# PCB_-_MODULE.net
KiCad netlist of a schematic drawn in EAGLE
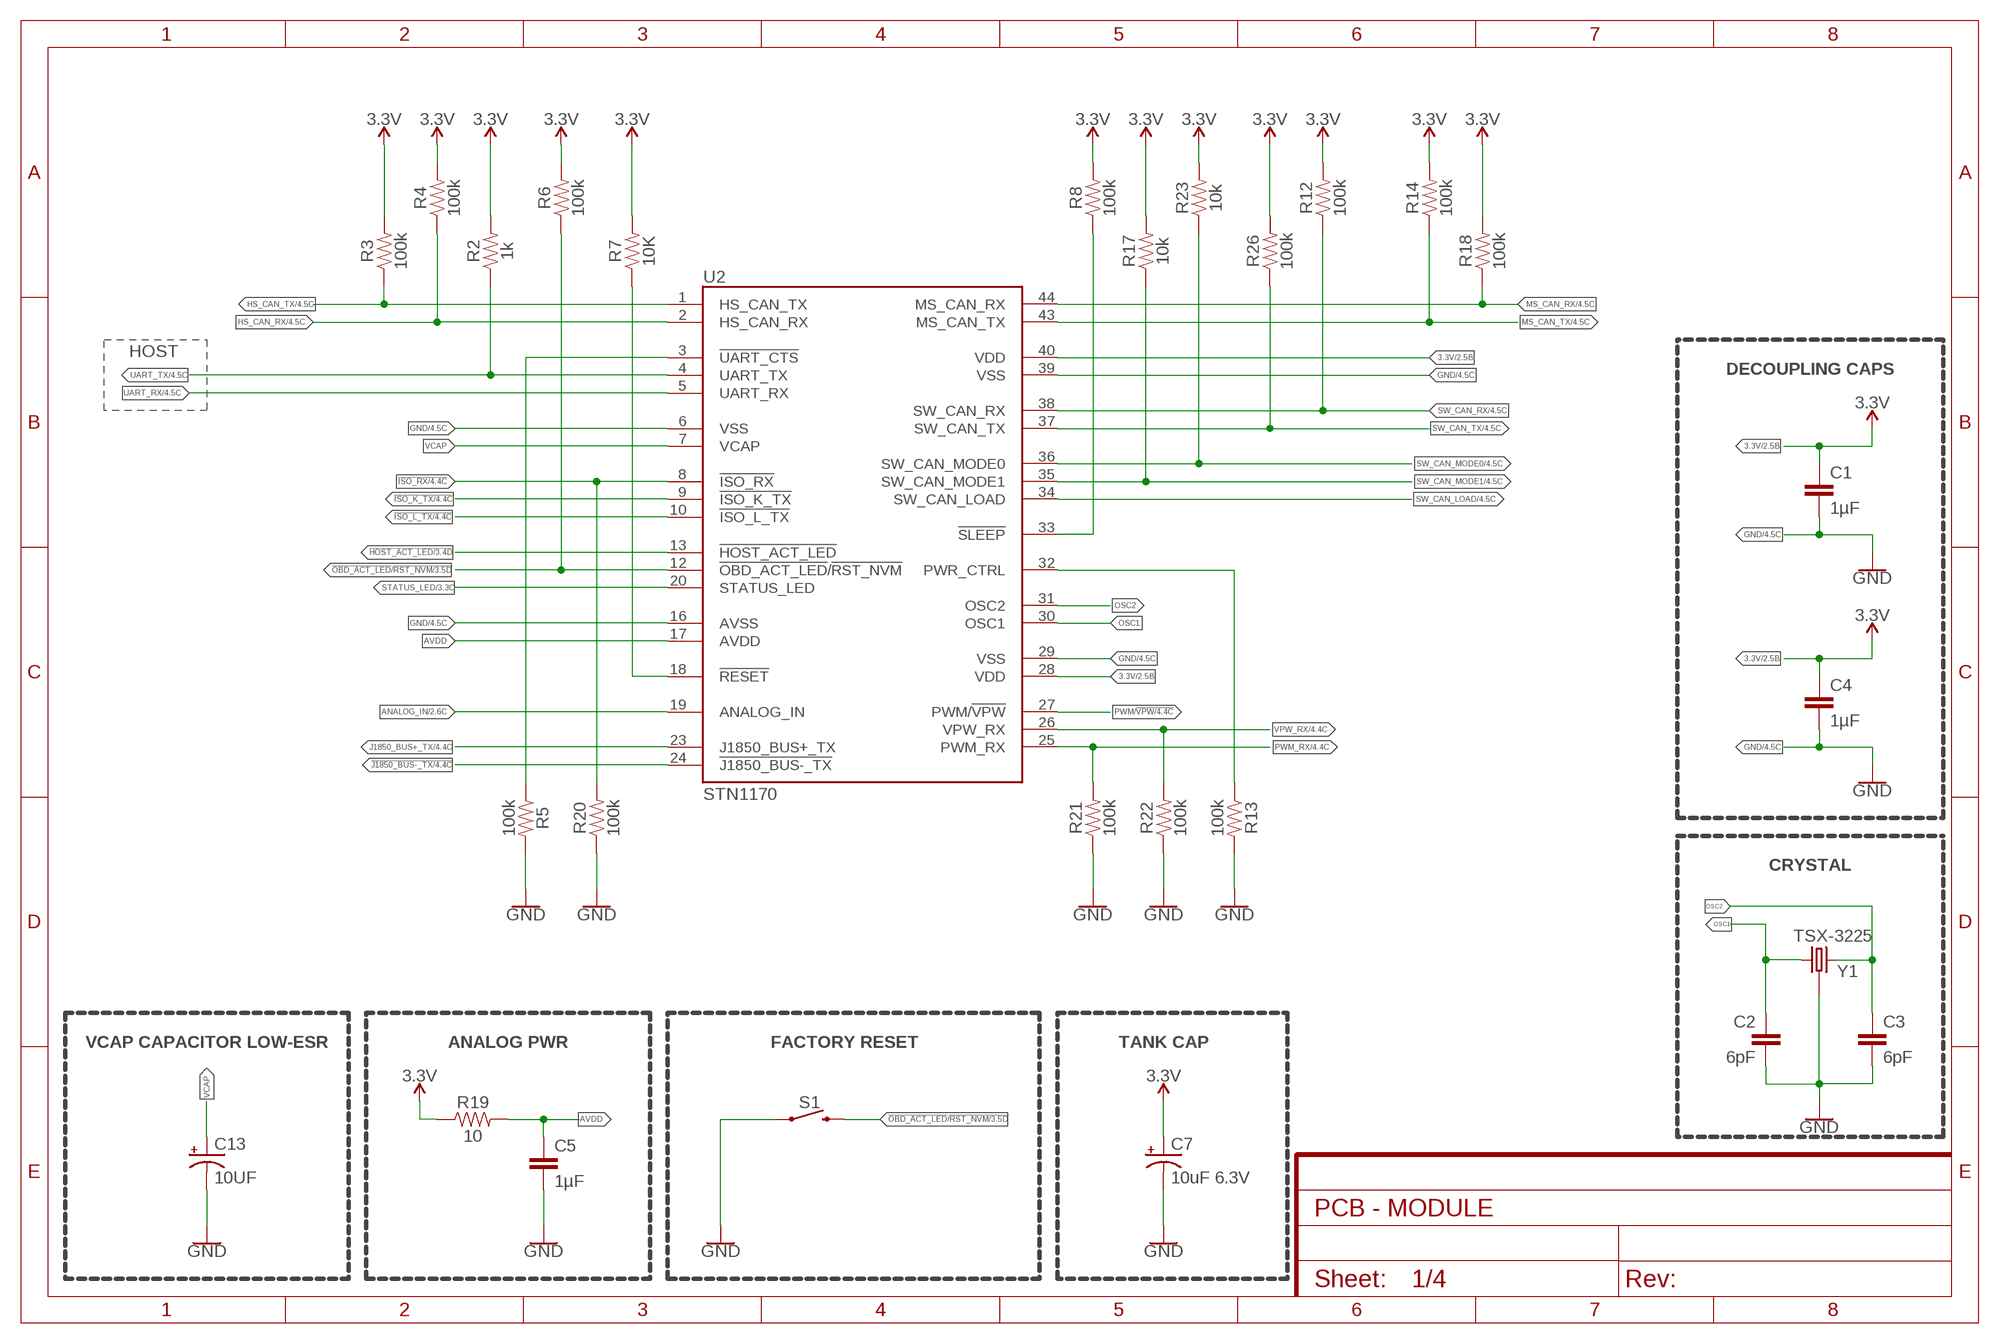
[diagram p0: schematic, sheet 1]
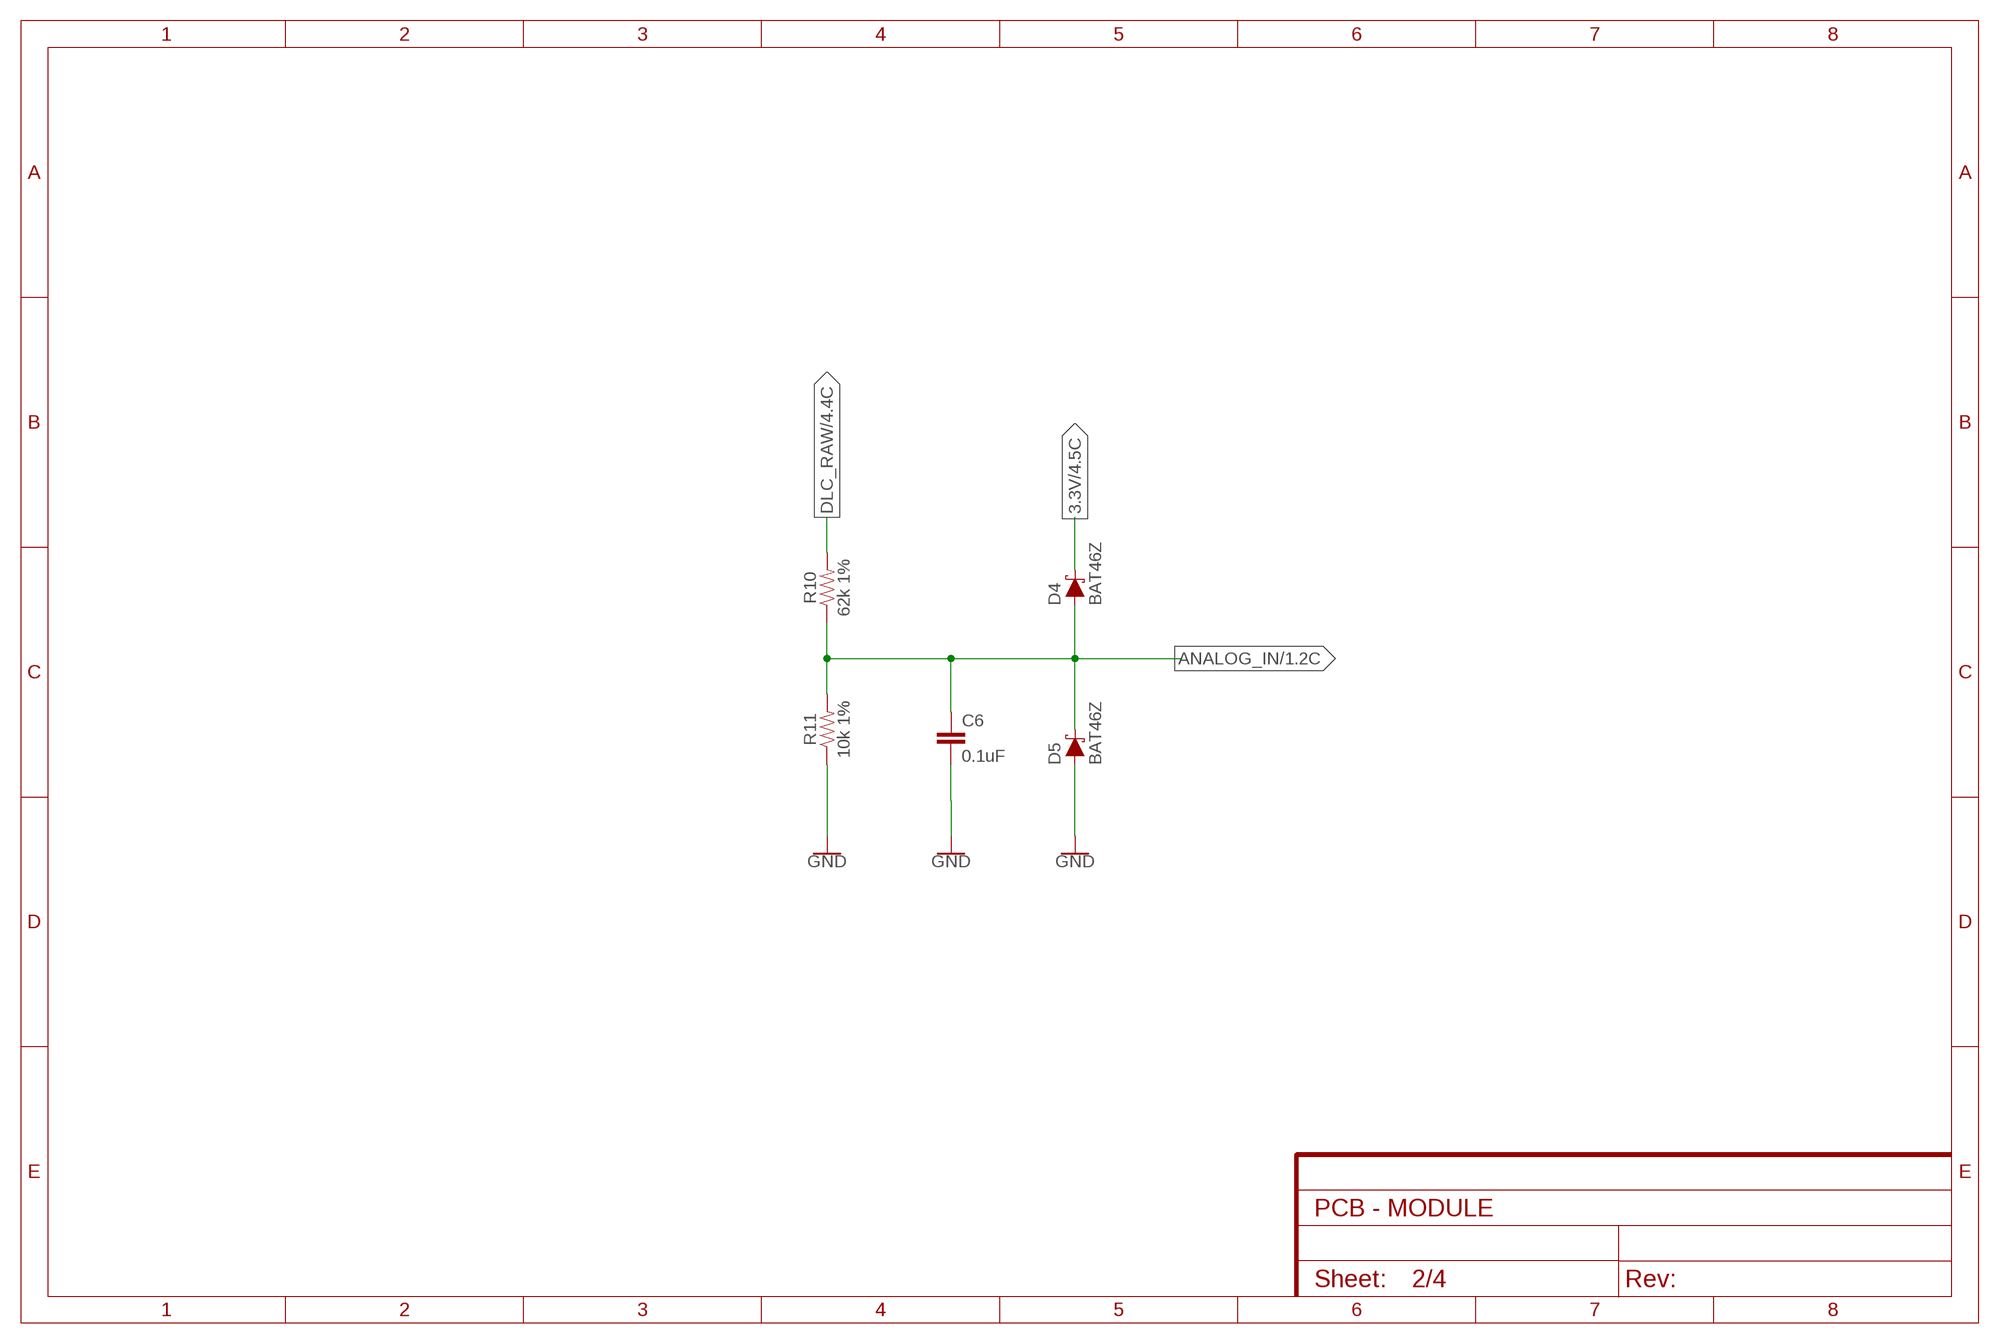
[diagram p1: schematic, sheet 2]
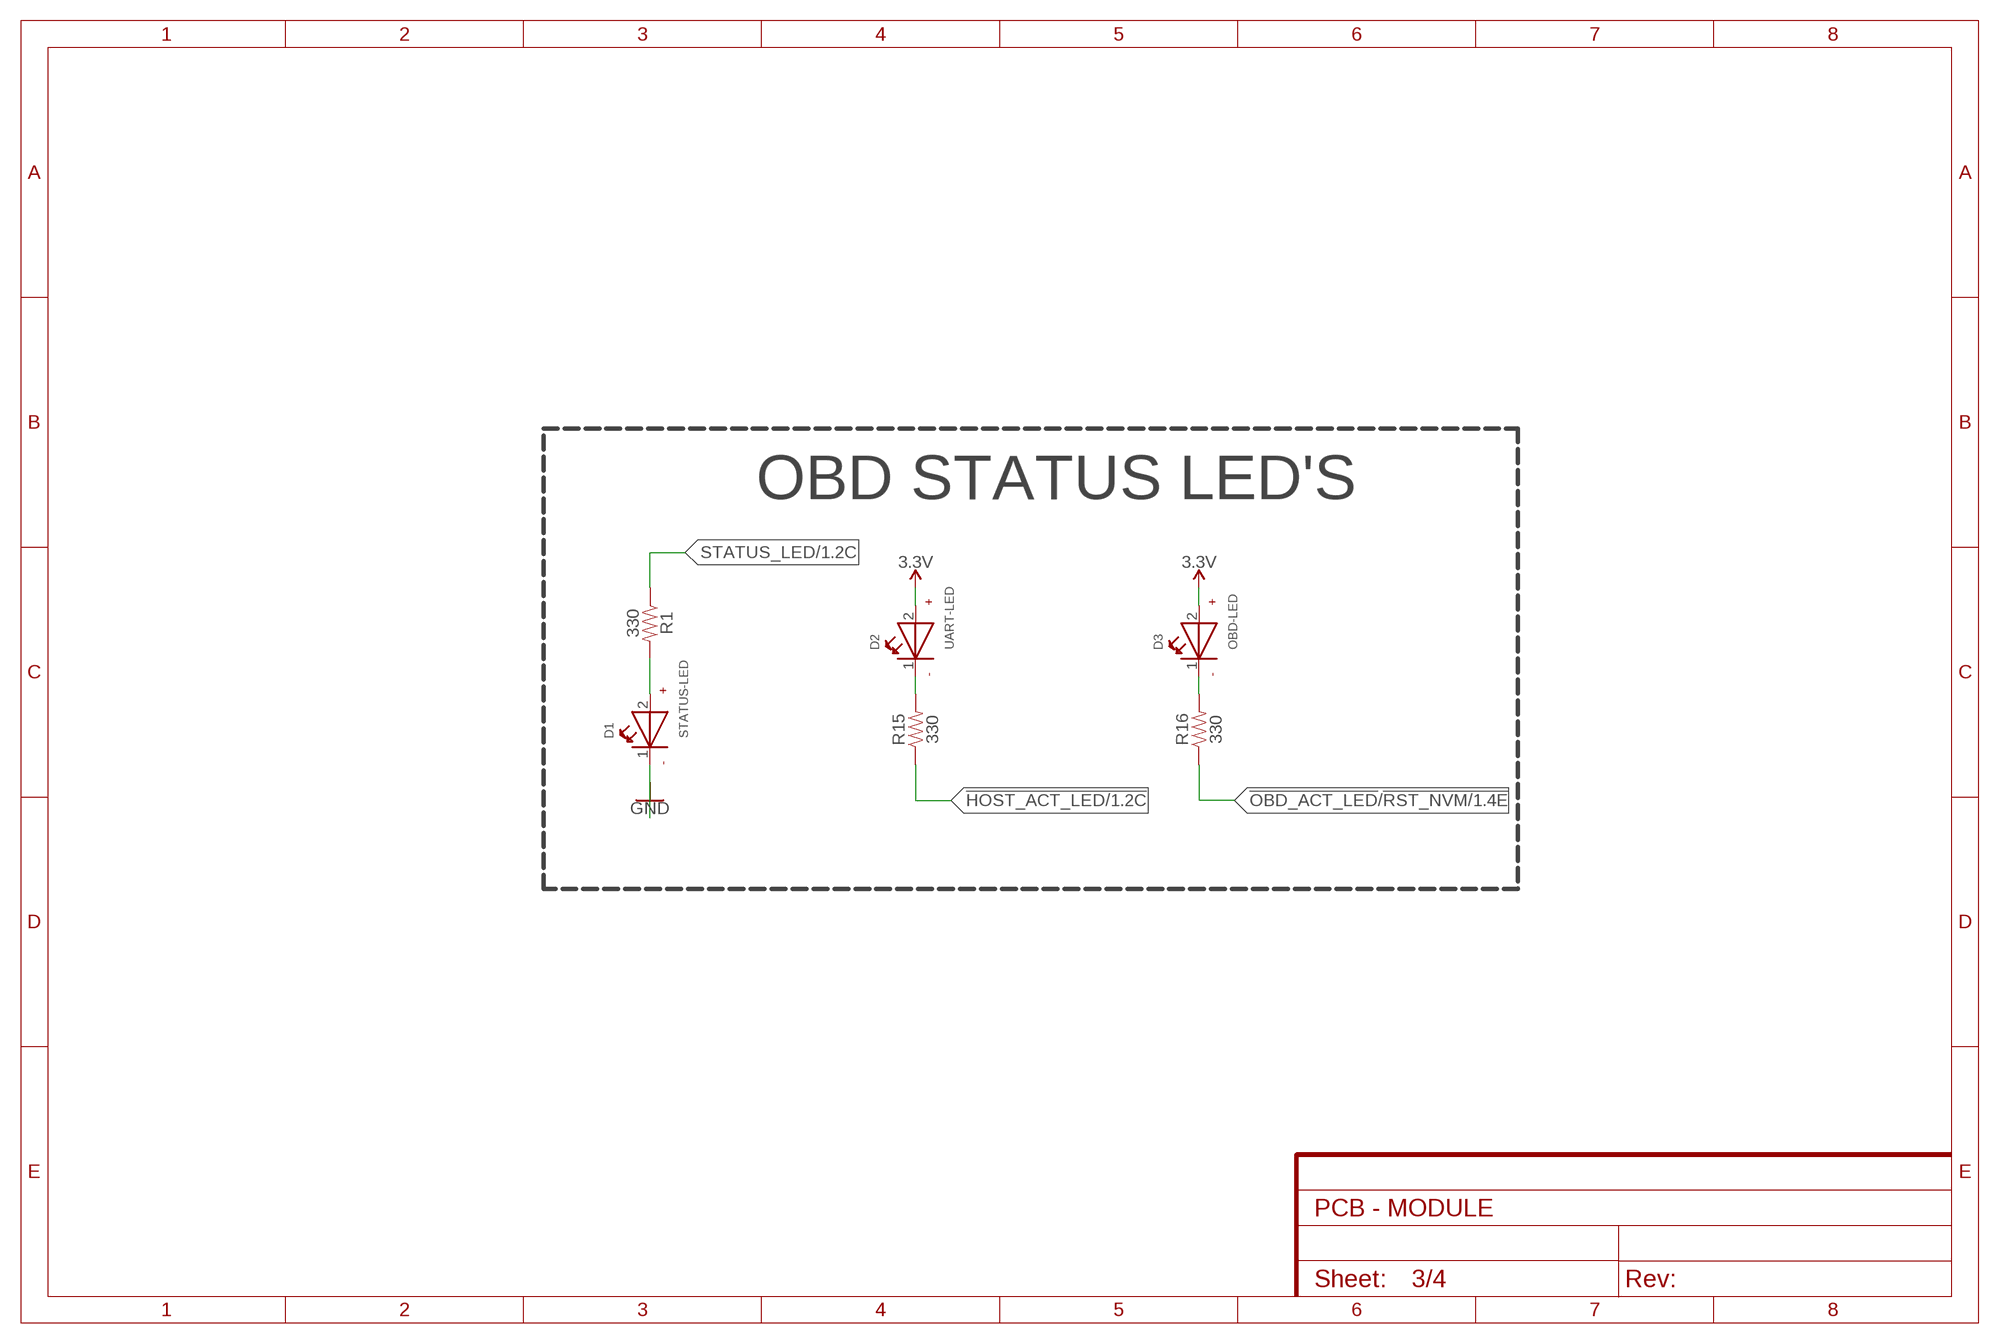
[diagram p2: schematic, sheet 3]
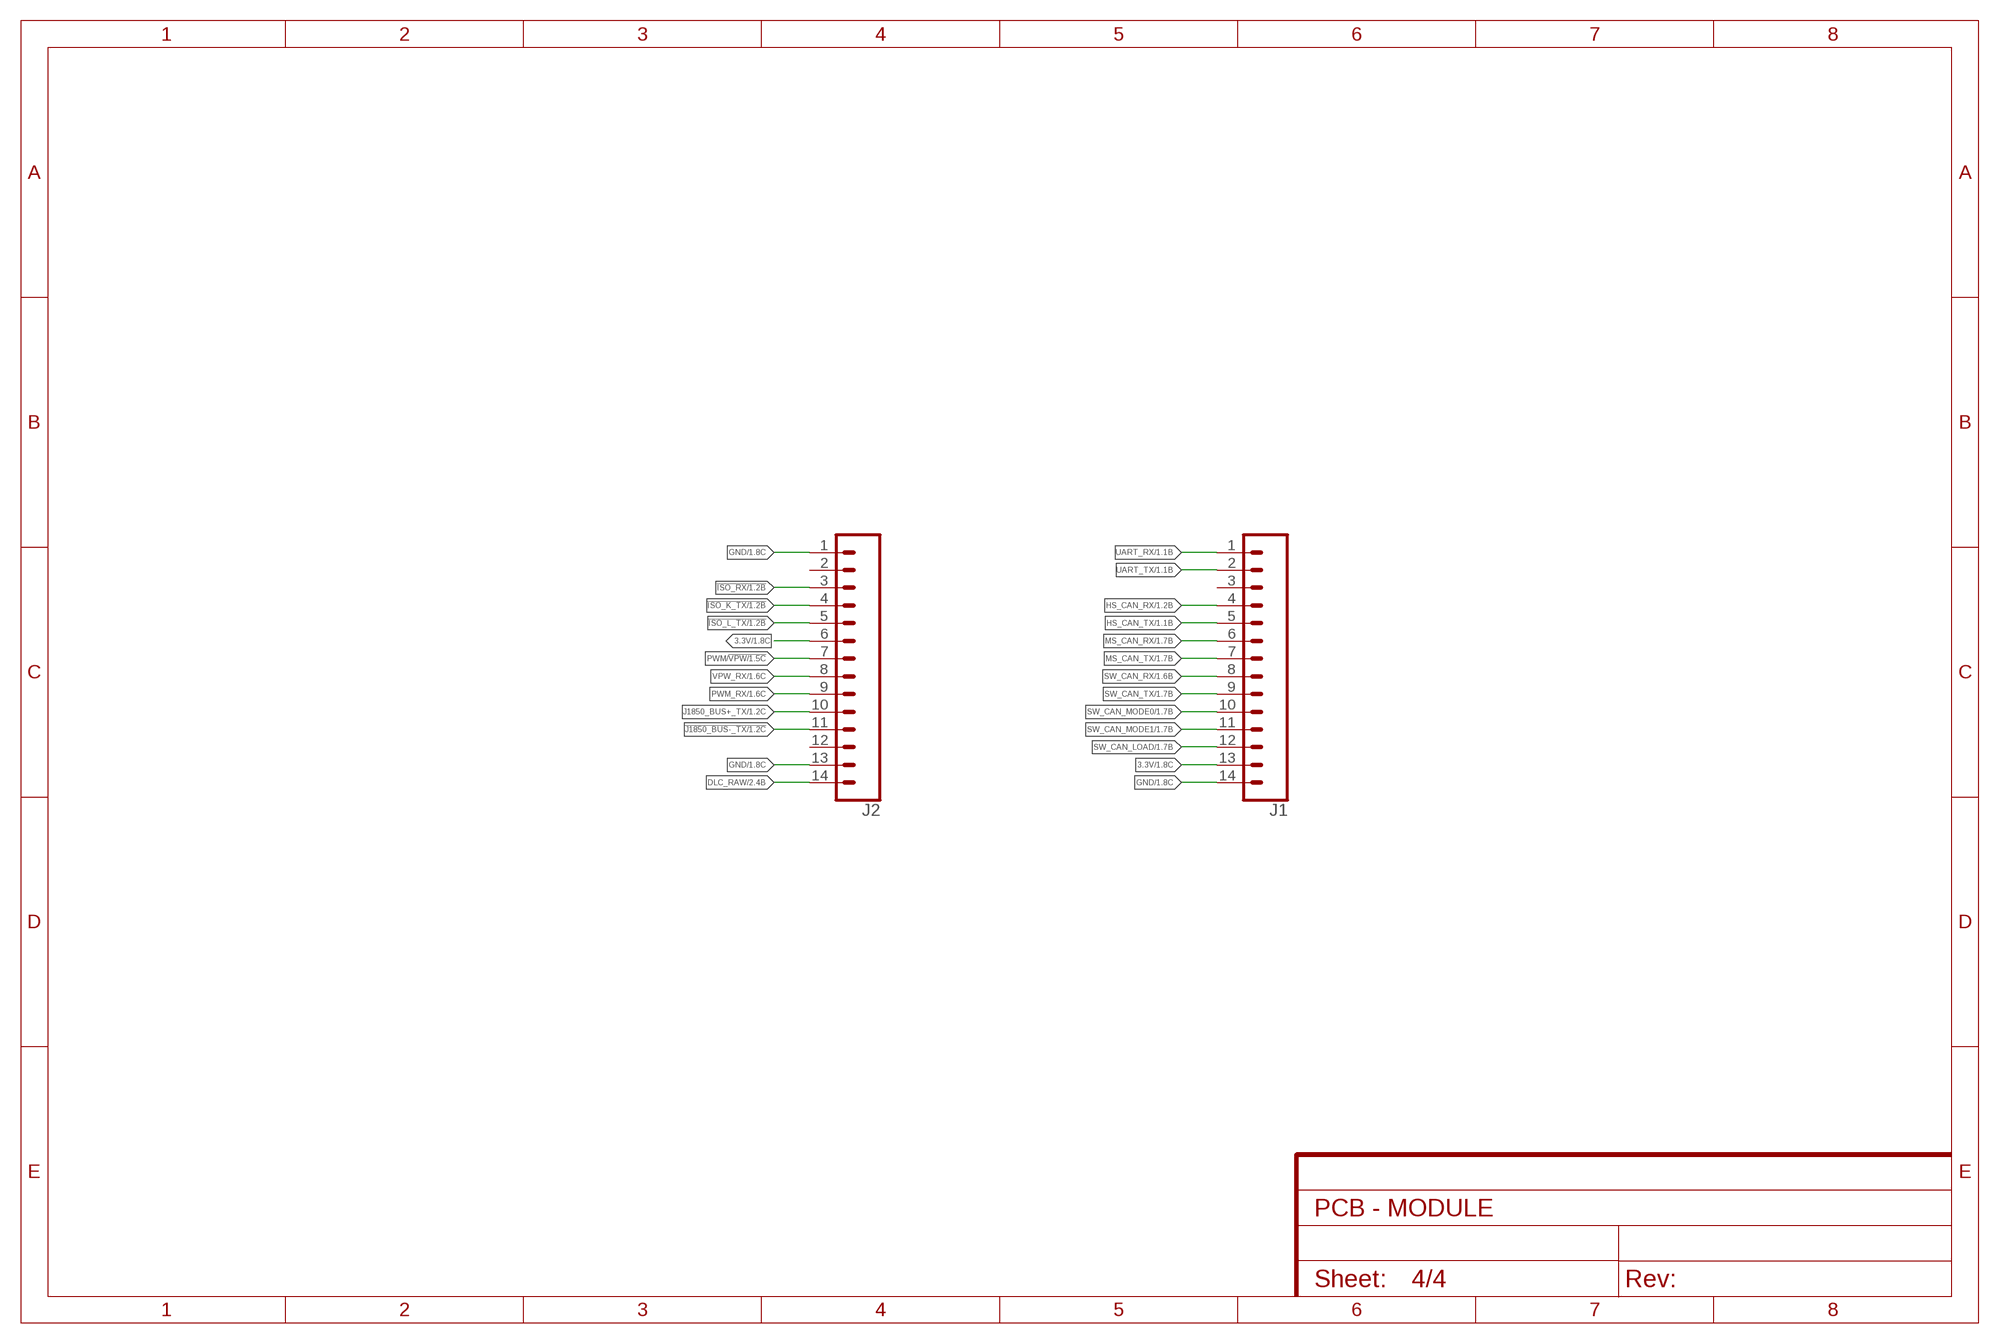
[diagram p3: schematic, sheet 4]

(export (version "E")
  (design (tool "Eeschema 10.0.6"))
  (components
    (comp (ref "C1")
      (value "1µF")
      (footprint "eagle-import:0805")
      (libsource (lib "eagle-import") (part "0.33UF/330NF-0805-50V-10%"))
    )
    (comp (ref "C2")
      (value "6pF")
      (footprint "eagle-import:0805")
      (libsource (lib "eagle-import") (part "0.33UF/330NF-0805-50V-10%"))
    )
    (comp (ref "C3")
      (value "6pF")
      (footprint "eagle-import:0805")
      (libsource (lib "eagle-import") (part "0.33UF/330NF-0805-50V-10%"))
    )
    (comp (ref "C4")
      (value "1µF")
      (footprint "eagle-import:0805")
      (libsource (lib "eagle-import") (part "0.33UF/330NF-0805-50V-10%"))
    )
    (comp (ref "C5")
      (value "1µF")
      (footprint "eagle-import:0805")
      (libsource (lib "eagle-import") (part "0.33UF/330NF-0805-50V-10%"))
    )
    (comp (ref "C7")
      (value "10uF 6.3V")
      (footprint "eagle-import:EIA3216")
      (libsource (lib "eagle-import") (part "10UF-POLAR-EIA3216-16V-10%(TANT)"))
    )
    (comp (ref "C13")
      (value "10UF")
      (footprint "eagle-import:1206")
      (libsource (lib "eagle-import") (part "10UF"))
    )
    (comp (ref "R2")
      (value "1k")
      (footprint "eagle-import:0805")
      (libsource (lib "eagle-import") (part "0.75OHM-0805-1/4W-1%"))
    )
    (comp (ref "R3")
      (value "100k")
      (footprint "eagle-import:0805")
      (libsource (lib "eagle-import") (part "0.75OHM-0805-1/4W-1%"))
    )
    (comp (ref "R4")
      (value "100k")
      (footprint "eagle-import:0805")
      (libsource (lib "eagle-import") (part "0.75OHM-0805-1/4W-1%"))
    )
    (comp (ref "R5")
      (value "100k")
      (footprint "eagle-import:0805")
      (libsource (lib "eagle-import") (part "0.75OHM-0805-1/4W-1%"))
    )
    (comp (ref "R6")
      (value "100k")
      (footprint "eagle-import:0805")
      (libsource (lib "eagle-import") (part "0.75OHM-0805-1/4W-1%"))
    )
    (comp (ref "R7")
      (value "10K")
      (footprint "eagle-import:0805")
      (libsource (lib "eagle-import") (part "0.75OHM-0805-1/4W-1%"))
    )
    (comp (ref "R8")
      (value "100k")
      (footprint "eagle-import:0805")
      (libsource (lib "eagle-import") (part "0.75OHM-0805-1/4W-1%"))
    )
    (comp (ref "R12")
      (value "100k")
      (footprint "eagle-import:0805")
      (libsource (lib "eagle-import") (part "0.75OHM-0805-1/4W-1%"))
    )
    (comp (ref "R13")
      (value "100k")
      (footprint "eagle-import:0805")
      (libsource (lib "eagle-import") (part "0.75OHM-0805-1/4W-1%"))
    )
    (comp (ref "R14")
      (value "100k")
      (footprint "eagle-import:0805")
      (libsource (lib "eagle-import") (part "0.75OHM-0805-1/4W-1%"))
    )
    (comp (ref "R17")
      (value "10k")
      (footprint "eagle-import:0805")
      (libsource (lib "eagle-import") (part "0.75OHM-0805-1/4W-1%"))
    )
    (comp (ref "R18")
      (value "100k")
      (footprint "eagle-import:0805")
      (libsource (lib "eagle-import") (part "0.75OHM-0805-1/4W-1%"))
    )
    (comp (ref "R19")
      (value "10")
      (footprint "eagle-import:0805")
      (libsource (lib "eagle-import") (part "0.75OHM-0805-1/4W-1%"))
    )
    (comp (ref "R20")
      (value "100k")
      (footprint "eagle-import:0805")
      (libsource (lib "eagle-import") (part "0.75OHM-0805-1/4W-1%"))
    )
    (comp (ref "R21")
      (value "100k")
      (footprint "eagle-import:0805")
      (libsource (lib "eagle-import") (part "0.75OHM-0805-1/4W-1%"))
    )
    (comp (ref "R22")
      (value "100k")
      (footprint "eagle-import:0805")
      (libsource (lib "eagle-import") (part "0.75OHM-0805-1/4W-1%"))
    )
    (comp (ref "R23")
      (value "10k")
      (footprint "eagle-import:0805")
      (libsource (lib "eagle-import") (part "0.75OHM-0805-1/4W-1%"))
    )
    (comp (ref "R26")
      (value "100k")
      (footprint "eagle-import:0805")
      (libsource (lib "eagle-import") (part "0.75OHM-0805-1/4W-1%"))
    )
    (comp (ref "S1")
      (value "B3U")
      (footprint "eagle-import:B3U-WO-GT-WO-B")
      (libsource (lib "eagle-import") (part "B3U"))
    )
    (comp (ref "U2")
      (value "STN1170")
      (footprint "eagle-import:TQFP44")
      (libsource (lib "eagle-import") (part "STN1170"))
    )
    (comp (ref "Y1")
      (value "TSX-3225")
      (footprint "eagle-import:TSX-3225-SOLDERING-IRON")
      (libsource (lib "eagle-import") (part "TSX-3225BIGGERPADS"))
    )
    (comp (ref "D1")
      (value "STATUS-LED")
      (footprint "eagle-import:WL-SMCW_1206")
      (libsource (lib "eagle-import") (part "WL-SMCW-150120RS75000-R"))
    )
    (comp (ref "D2")
      (value "UART-LED")
      (footprint "eagle-import:WL-SMCW_1206")
      (libsource (lib "eagle-import") (part "WL-SMCW-150120YS75000-Y"))
    )
    (comp (ref "D3")
      (value "OBD-LED")
      (footprint "eagle-import:WL-SMCW_1206")
      (libsource (lib "eagle-import") (part "WL-SMCW-150120GS75000-G"))
    )
    (comp (ref "R1")
      (value "330")
      (footprint "eagle-import:0805")
      (libsource (lib "eagle-import") (part "0.75OHM-0805-1/4W-1%"))
    )
    (comp (ref "R15")
      (value "330")
      (footprint "eagle-import:0805")
      (libsource (lib "eagle-import") (part "0.75OHM-0805-1/4W-1%"))
    )
    (comp (ref "R16")
      (value "330")
      (footprint "eagle-import:0805")
      (libsource (lib "eagle-import") (part "0.75OHM-0805-1/4W-1%"))
    )
    (comp (ref "C6")
      (value "0.1uF")
      (footprint "eagle-import:0805")
      (libsource (lib "eagle-import") (part "0.33UF/330NF-0805-50V-10%"))
    )
    (comp (ref "D4")
      (value "BAT46Z")
      (footprint "eagle-import:SOD-123")
      (libsource (lib "eagle-import") (part "BAT46Z"))
    )
    (comp (ref "D5")
      (value "BAT46Z")
      (footprint "eagle-import:SOD-123")
      (libsource (lib "eagle-import") (part "BAT46Z"))
    )
    (comp (ref "R10")
      (value "62k 1%")
      (footprint "eagle-import:0805")
      (libsource (lib "eagle-import") (part "0.75OHM-0805-1/4W-1%"))
    )
    (comp (ref "R11")
      (value "10k 1%")
      (footprint "eagle-import:0805")
      (libsource (lib "eagle-import") (part "0.75OHM-0805-1/4W-1%"))
    )
    (comp (ref "J1")
      (value "CONN_14")
      (footprint "eagle-import:1X14")
      (libsource (lib "eagle-import") (part "CONN_14"))
    )
    (comp (ref "J2")
      (value "CONN_14")
      (footprint "eagle-import:1X14")
      (libsource (lib "eagle-import") (part "CONN_14"))
    )
  )
  (nets
    (net (code "1") (name "3.3V") (class "Default")
      (node (ref "C1") (pin "1") (pinfunction "1_1") (pintype "passive"))
      (node (ref "C4") (pin "1") (pinfunction "1_1") (pintype "passive"))
      (node (ref "C7") (pin "+") (pinfunction "+_+") (pintype "passive"))
      (node (ref "D2") (pin "2") (pinfunction "+_2") (pintype "passive"))
      (node (ref "D3") (pin "2") (pinfunction "+_2") (pintype "passive"))
      (node (ref "D4") (pin "C") (pinfunction "C_C") (pintype "passive"))
      (node (ref "J1") (pin "13") (pinfunction "13_13") (pintype "passive"))
      (node (ref "J2") (pin "6") (pinfunction "6_6") (pintype "passive"))
      (node (ref "R12") (pin "2") (pinfunction "2_2") (pintype "passive"))
      (node (ref "R14") (pin "2") (pinfunction "2_2") (pintype "passive"))
      (node (ref "R17") (pin "2") (pinfunction "2_2") (pintype "passive"))
      (node (ref "R18") (pin "2") (pinfunction "2_2") (pintype "passive"))
      (node (ref "R19") (pin "1") (pinfunction "1_1") (pintype "passive"))
      (node (ref "R2") (pin "2") (pinfunction "2_2") (pintype "passive"))
      (node (ref "R23") (pin "2") (pinfunction "2_2") (pintype "passive"))
      (node (ref "R26") (pin "2") (pinfunction "2_2") (pintype "passive"))
      (node (ref "R3") (pin "2") (pinfunction "2_2") (pintype "passive"))
      (node (ref "R4") (pin "2") (pinfunction "2_2") (pintype "passive"))
      (node (ref "R6") (pin "2") (pinfunction "2_2") (pintype "passive"))
      (node (ref "R7") (pin "2") (pinfunction "2_2") (pintype "passive"))
      (node (ref "R8") (pin "2") (pinfunction "2_2") (pintype "passive"))
      (node (ref "U2") (pin "28") (pinfunction "VDD_28") (pintype "power_in"))
      (node (ref "U2") (pin "40") (pinfunction "VDD_40") (pintype "power_in"))
    )
    (net (code "2") (name "ANALOG_IN") (class "Default")
      (node (ref "C6") (pin "1") (pinfunction "1_1") (pintype "passive"))
      (node (ref "D4") (pin "A") (pinfunction "A_A") (pintype "passive"))
      (node (ref "D5") (pin "C") (pinfunction "C_C") (pintype "passive"))
      (node (ref "R10") (pin "1") (pinfunction "1_1") (pintype "passive"))
      (node (ref "R11") (pin "2") (pinfunction "2_2") (pintype "passive"))
      (node (ref "U2") (pin "19") (pinfunction "ANALOG_IN_19") (pintype "input"))
    )
    (net (code "3") (name "AVDD") (class "Default")
      (node (ref "C5") (pin "1") (pinfunction "1_1") (pintype "passive"))
      (node (ref "R19") (pin "2") (pinfunction "2_2") (pintype "passive"))
      (node (ref "U2") (pin "17") (pinfunction "AVDD_17") (pintype "power_in"))
    )
    (net (code "4") (name "DLC_RAW") (class "Default")
      (node (ref "J2") (pin "14") (pinfunction "14_14") (pintype "passive"))
      (node (ref "R10") (pin "2") (pinfunction "2_2") (pintype "passive"))
    )
    (net (code "5") (name "GND") (class "Default")
      (node (ref "C1") (pin "2") (pinfunction "2_2") (pintype "passive"))
      (node (ref "C13") (pin "2") (pinfunction "-_2") (pintype "passive"))
      (node (ref "C2") (pin "2") (pinfunction "2_2") (pintype "passive"))
      (node (ref "C3") (pin "2") (pinfunction "2_2") (pintype "passive"))
      (node (ref "C4") (pin "2") (pinfunction "2_2") (pintype "passive"))
      (node (ref "C5") (pin "2") (pinfunction "2_2") (pintype "passive"))
      (node (ref "C6") (pin "2") (pinfunction "2_2") (pintype "passive"))
      (node (ref "C7") (pin "-") (pinfunction "-_-") (pintype "passive"))
      (node (ref "D1") (pin "1") (pinfunction "-_1") (pintype "passive"))
      (node (ref "D5") (pin "A") (pinfunction "A_A") (pintype "passive"))
      (node (ref "J1") (pin "14") (pinfunction "14_14") (pintype "passive"))
      (node (ref "J2") (pin "1") (pinfunction "1_1") (pintype "passive"))
      (node (ref "J2") (pin "13") (pinfunction "13_13") (pintype "passive"))
      (node (ref "R11") (pin "1") (pinfunction "1_1") (pintype "passive"))
      (node (ref "R13") (pin "2") (pinfunction "2_2") (pintype "passive"))
      (node (ref "R20") (pin "1") (pinfunction "1_1") (pintype "passive"))
      (node (ref "R21") (pin "1") (pinfunction "1_1") (pintype "passive"))
      (node (ref "R22") (pin "1") (pinfunction "1_1") (pintype "passive"))
      (node (ref "R5") (pin "2") (pinfunction "2_2") (pintype "passive"))
      (node (ref "S1") (pin "1") (pinfunction "1_1") (pintype "passive"))
      (node (ref "U2") (pin "16") (pinfunction "AVSS_16") (pintype "power_in"))
      (node (ref "U2") (pin "29") (pinfunction "VSS_29") (pintype "power_in"))
      (node (ref "U2") (pin "39") (pinfunction "VSS_39") (pintype "power_in"))
      (node (ref "U2") (pin "6") (pinfunction "VSS_6") (pintype "power_in"))
      (node (ref "Y1") (pin "2") (pinfunction "3_2") (pintype "passive"))
      (node (ref "Y1") (pin "4") (pinfunction "3_4") (pintype "passive"))
    )
    (net (code "6") (name "HS_CAN_RX") (class "Default")
      (node (ref "J1") (pin "4") (pinfunction "4_4") (pintype "passive"))
      (node (ref "R4") (pin "1") (pinfunction "1_1") (pintype "passive"))
      (node (ref "U2") (pin "2") (pinfunction "HS_CAN_RX_2") (pintype "input"))
    )
    (net (code "7") (name "HS_CAN_TX") (class "Default")
      (node (ref "J1") (pin "5") (pinfunction "5_5") (pintype "passive"))
      (node (ref "R3") (pin "1") (pinfunction "1_1") (pintype "passive"))
      (node (ref "U2") (pin "1") (pinfunction "HS_CAN_TX_1") (pintype "input"))
    )
    (net (code "8") (name "J1850_BUS+_TX") (class "Default")
      (node (ref "J2") (pin "10") (pinfunction "10_10") (pintype "passive"))
      (node (ref "U2") (pin "23") (pinfunction "J1850_BUS+_TX_23") (pintype "output"))
    )
    (net (code "9") (name "MS_CAN_RX") (class "Default")
      (node (ref "J1") (pin "6") (pinfunction "6_6") (pintype "passive"))
      (node (ref "R18") (pin "1") (pinfunction "1_1") (pintype "passive"))
      (node (ref "U2") (pin "44") (pinfunction "MS_CAN_RX_44") (pintype "input"))
    )
    (net (code "10") (name "MS_CAN_TX") (class "Default")
      (node (ref "J1") (pin "7") (pinfunction "7_7") (pintype "passive"))
      (node (ref "R14") (pin "1") (pinfunction "1_1") (pintype "passive"))
      (node (ref "U2") (pin "43") (pinfunction "MS_CAN_TX_43") (pintype "output"))
    )
    (net (code "11") (name "Net-(D1-+)") (class "Default")
      (node (ref "D1") (pin "2") (pinfunction "+_2") (pintype "passive"))
      (node (ref "R1") (pin "2") (pinfunction "2_2") (pintype "passive"))
    )
    (net (code "12") (name "Net-(D2--)") (class "Default")
      (node (ref "D2") (pin "1") (pinfunction "-_1") (pintype "passive"))
      (node (ref "R15") (pin "2") (pinfunction "2_2") (pintype "passive"))
    )
    (net (code "13") (name "Net-(D3--)") (class "Default")
      (node (ref "D3") (pin "1") (pinfunction "-_1") (pintype "passive"))
      (node (ref "R16") (pin "2") (pinfunction "2_2") (pintype "passive"))
    )
    (net (code "14") (name "Net-(U2-PWR_CTRL)") (class "Default")
      (node (ref "R13") (pin "1") (pinfunction "1_1") (pintype "passive"))
      (node (ref "U2") (pin "32") (pinfunction "PWR_CTRL_32") (pintype "output"))
    )
    (net (code "15") (name "Net-(U2-~{RESET})") (class "Default")
      (node (ref "R7") (pin "1") (pinfunction "1_1") (pintype "passive"))
      (node (ref "U2") (pin "18") (pinfunction "~{RESET}_18") (pintype "input"))
    )
    (net (code "16") (name "Net-(U2-~{SLEEP})") (class "Default")
      (node (ref "R8") (pin "1") (pinfunction "1_1") (pintype "passive"))
      (node (ref "U2") (pin "33") (pinfunction "~{SLEEP}_33") (pintype "input"))
    )
    (net (code "17") (name "Net-(U2-~{UART_CTS})") (class "Default")
      (node (ref "R5") (pin "1") (pinfunction "1_1") (pintype "passive"))
      (node (ref "U2") (pin "3") (pinfunction "~{UART_CTS}_3") (pintype "input"))
    )
    (net (code "18") (name "OSC1") (class "Default")
      (node (ref "C2") (pin "1") (pinfunction "1_1") (pintype "passive"))
      (node (ref "U2") (pin "30") (pinfunction "OSC1_30") (pintype "input"))
      (node (ref "Y1") (pin "1") (pinfunction "1_1") (pintype "passive"))
    )
    (net (code "19") (name "OSC2") (class "Default")
      (node (ref "C3") (pin "1") (pinfunction "1_1") (pintype "passive"))
      (node (ref "U2") (pin "31") (pinfunction "OSC2_31") (pintype "output"))
      (node (ref "Y1") (pin "3") (pinfunction "2_3") (pintype "passive"))
    )
    (net (code "20") (name "PWM_RX") (class "Default")
      (node (ref "J2") (pin "9") (pinfunction "9_9") (pintype "passive"))
      (node (ref "R21") (pin "2") (pinfunction "2_2") (pintype "passive"))
      (node (ref "U2") (pin "25") (pinfunction "PWM_RX_25") (pintype "input"))
    )
    (net (code "21") (name "PWM{slash}~{VPW}") (class "Default")
      (node (ref "J2") (pin "7") (pinfunction "7_7") (pintype "passive"))
      (node (ref "U2") (pin "27") (pinfunction "PWM/~{VPW}_27") (pintype "output"))
    )
    (net (code "22") (name "STATUS_LED") (class "Default")
      (node (ref "R1") (pin "1") (pinfunction "1_1") (pintype "passive"))
      (node (ref "U2") (pin "20") (pinfunction "STATUS_LED_20") (pintype "output"))
    )
    (net (code "23") (name "SW_CAN_LOAD") (class "Default")
      (node (ref "J1") (pin "12") (pinfunction "12_12") (pintype "passive"))
      (node (ref "U2") (pin "34") (pinfunction "SW_CAN_LOAD_34") (pintype "output"))
    )
    (net (code "24") (name "SW_CAN_MODE0") (class "Default")
      (node (ref "J1") (pin "10") (pinfunction "10_10") (pintype "passive"))
      (node (ref "R23") (pin "1") (pinfunction "1_1") (pintype "passive"))
      (node (ref "U2") (pin "36") (pinfunction "SW_CAN_MODE0_36") (pintype "output"))
    )
    (net (code "25") (name "SW_CAN_MODE1") (class "Default")
      (node (ref "J1") (pin "11") (pinfunction "11_11") (pintype "passive"))
      (node (ref "R17") (pin "1") (pinfunction "1_1") (pintype "passive"))
      (node (ref "U2") (pin "35") (pinfunction "SW_CAN_MODE1_35") (pintype "output"))
    )
    (net (code "26") (name "SW_CAN_RX") (class "Default")
      (node (ref "J1") (pin "8") (pinfunction "8_8") (pintype "passive"))
      (node (ref "R12") (pin "1") (pinfunction "1_1") (pintype "passive"))
      (node (ref "U2") (pin "38") (pinfunction "SW_CAN_RX_38") (pintype "input"))
    )
    (net (code "27") (name "SW_CAN_TX") (class "Default")
      (node (ref "J1") (pin "9") (pinfunction "9_9") (pintype "passive"))
      (node (ref "R26") (pin "1") (pinfunction "1_1") (pintype "passive"))
      (node (ref "U2") (pin "37") (pinfunction "SW_CAN_TX_37") (pintype "output"))
    )
    (net (code "28") (name "UART_RX") (class "Default")
      (node (ref "J1") (pin "1") (pinfunction "1_1") (pintype "passive"))
      (node (ref "U2") (pin "5") (pinfunction "UART_RX_5") (pintype "input"))
    )
    (net (code "29") (name "UART_TX") (class "Default")
      (node (ref "J1") (pin "2") (pinfunction "2_2") (pintype "passive"))
      (node (ref "R2") (pin "1") (pinfunction "1_1") (pintype "passive"))
      (node (ref "U2") (pin "4") (pinfunction "UART_TX_4") (pintype "output"))
    )
    (net (code "30") (name "VCAP") (class "Default")
      (node (ref "C13") (pin "1") (pinfunction "+_1") (pintype "passive"))
      (node (ref "U2") (pin "7") (pinfunction "VCAP_7") (pintype "power_in"))
    )
    (net (code "31") (name "VPW_RX") (class "Default")
      (node (ref "J2") (pin "8") (pinfunction "8_8") (pintype "passive"))
      (node (ref "R22") (pin "2") (pinfunction "2_2") (pintype "passive"))
      (node (ref "U2") (pin "26") (pinfunction "VPW_RX_26") (pintype "input"))
    )
    (net (code "32") (name "unconnected-(J1-Pad3)") (class "Default")
      (node (ref "J1") (pin "3") (pinfunction "3_3") (pintype "passive"))
    )
    (net (code "33") (name "unconnected-(J2-Pad2)") (class "Default")
      (node (ref "J2") (pin "2") (pinfunction "2_2") (pintype "passive"))
    )
    (net (code "34") (name "unconnected-(J2-Pad12)") (class "Default")
      (node (ref "J2") (pin "12") (pinfunction "12_12") (pintype "passive"))
    )
    (net (code "35") (name "~{HOST_ACT_LED}") (class "Default")
      (node (ref "R15") (pin "1") (pinfunction "1_1") (pintype "passive"))
      (node (ref "U2") (pin "13") (pinfunction "~{HOST_ACT_LED}_13") (pintype "output"))
    )
    (net (code "36") (name "~{ISO_K_TX}") (class "Default")
      (node (ref "J2") (pin "4") (pinfunction "4_4") (pintype "passive"))
      (node (ref "U2") (pin "9") (pinfunction "~{ISO_K_TX}_9") (pintype "output"))
    )
    (net (code "37") (name "~{ISO_L_TX}") (class "Default")
      (node (ref "J2") (pin "5") (pinfunction "5_5") (pintype "passive"))
      (node (ref "U2") (pin "10") (pinfunction "~{ISO_L_TX}_10") (pintype "output"))
    )
    (net (code "38") (name "~{ISO_RX}") (class "Default")
      (node (ref "J2") (pin "3") (pinfunction "3_3") (pintype "passive"))
      (node (ref "R20") (pin "2") (pinfunction "2_2") (pintype "passive"))
      (node (ref "U2") (pin "8") (pinfunction "~{ISO_RX}_8") (pintype "input"))
    )
    (net (code "39") (name "~{J1850_BUS-_TX}") (class "Default")
      (node (ref "J2") (pin "11") (pinfunction "11_11") (pintype "passive"))
      (node (ref "U2") (pin "24") (pinfunction "~{J1850_BUS-_TX}_24") (pintype "output"))
    )
    (net (code "40") (name "~{OBD_ACT_LED}{slash}~{RST_NVM}") (class "Default")
      (node (ref "R16") (pin "1") (pinfunction "1_1") (pintype "passive"))
      (node (ref "R6") (pin "1") (pinfunction "1_1") (pintype "passive"))
      (node (ref "S1") (pin "2") (pinfunction "2_2") (pintype "passive"))
      (node (ref "U2") (pin "12") (pinfunction "~{OBD_ACT_LED}/~{RST_NVM}_12") (pintype "output"))
    )
  )
)
